# TDA2004.net
KiCad netlist of a schematic drawn in Altium Designer
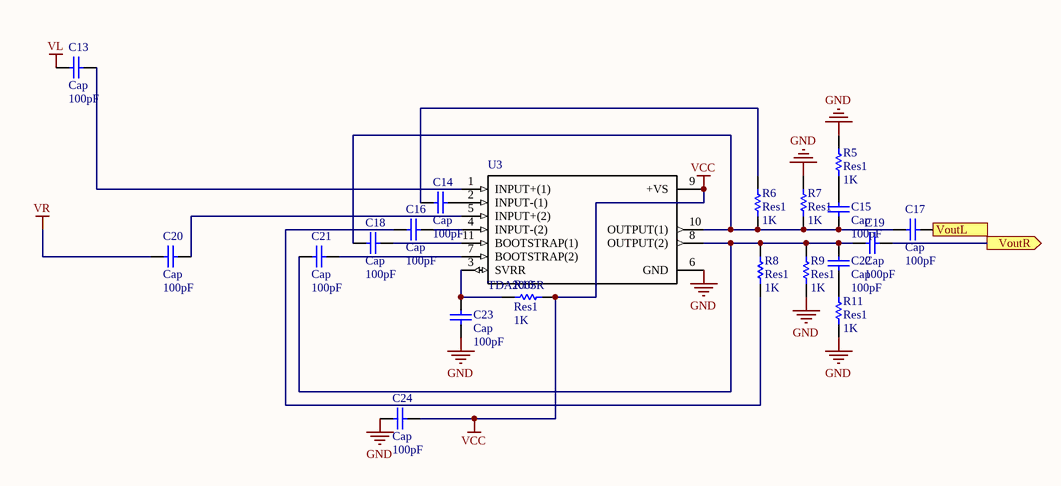
[diagram p0: TDA2004.SchDoc]

(export (version "E")
  (design (tool "Eeschema 10.0.6"))
  (components
    (comp (ref "C13")
      (value "Cap")
      (footprint "RAD-0.3")
      (description "Capacitor")
      (fields (field (name "ALTIUM_VALUE") "100pF") (field (name "PUBLISHER") "Altium Limited"))
      (libsource (lib "Miscellaneous Devices") (part "Cap"))
    )
    (comp (ref "C14")
      (value "Cap")
      (footprint "RAD-0.3")
      (description "Capacitor")
      (fields (field (name "ALTIUM_VALUE") "100pF") (field (name "PUBLISHER") "Altium Limited"))
      (libsource (lib "Miscellaneous Devices") (part "Cap"))
    )
    (comp (ref "C15")
      (value "Cap")
      (footprint "RAD-0.3")
      (description "Capacitor")
      (fields (field (name "ALTIUM_VALUE") "100pF") (field (name "PUBLISHER") "Altium Limited"))
      (libsource (lib "Miscellaneous Devices") (part "Cap"))
    )
    (comp (ref "C16")
      (value "Cap")
      (footprint "RAD-0.3")
      (description "Capacitor")
      (fields (field (name "ALTIUM_VALUE") "100pF") (field (name "PUBLISHER") "Altium Limited"))
      (libsource (lib "Miscellaneous Devices") (part "Cap"))
    )
    (comp (ref "C17")
      (value "Cap")
      (footprint "RAD-0.3")
      (description "Capacitor")
      (fields (field (name "ALTIUM_VALUE") "100pF") (field (name "PUBLISHER") "Altium Limited"))
      (libsource (lib "Miscellaneous Devices") (part "Cap"))
    )
    (comp (ref "C18")
      (value "Cap")
      (footprint "RAD-0.3")
      (description "Capacitor")
      (fields (field (name "ALTIUM_VALUE") "100pF") (field (name "PUBLISHER") "Altium Limited"))
      (libsource (lib "Miscellaneous Devices") (part "Cap"))
    )
    (comp (ref "C19")
      (value "Cap")
      (footprint "RAD-0.3")
      (description "Capacitor")
      (fields (field (name "ALTIUM_VALUE") "100pF") (field (name "PUBLISHER") "Altium Limited"))
      (libsource (lib "Miscellaneous Devices") (part "Cap"))
    )
    (comp (ref "C20")
      (value "Cap")
      (footprint "RAD-0.3")
      (description "Capacitor")
      (fields (field (name "ALTIUM_VALUE") "100pF") (field (name "PUBLISHER") "Altium Limited"))
      (libsource (lib "Miscellaneous Devices") (part "Cap"))
    )
    (comp (ref "C21")
      (value "Cap")
      (footprint "RAD-0.3")
      (description "Capacitor")
      (fields (field (name "ALTIUM_VALUE") "100pF") (field (name "PUBLISHER") "Altium Limited"))
      (libsource (lib "Miscellaneous Devices") (part "Cap"))
    )
    (comp (ref "C22")
      (value "Cap")
      (footprint "RAD-0.3")
      (description "Capacitor")
      (fields (field (name "ALTIUM_VALUE") "100pF") (field (name "PUBLISHER") "Altium Limited"))
      (libsource (lib "Miscellaneous Devices") (part "Cap"))
    )
    (comp (ref "C23")
      (value "Cap")
      (footprint "RAD-0.3")
      (description "Capacitor")
      (fields (field (name "ALTIUM_VALUE") "100pF") (field (name "PUBLISHER") "Altium Limited"))
      (libsource (lib "Miscellaneous Devices") (part "Cap"))
    )
    (comp (ref "C24")
      (value "Cap")
      (footprint "RAD-0.3")
      (description "Capacitor")
      (fields (field (name "ALTIUM_VALUE") "100pF") (field (name "PUBLISHER") "Altium Limited"))
      (libsource (lib "Miscellaneous Devices") (part "Cap"))
    )
    (comp (ref "R5")
      (value "Res1")
      (footprint "AXIAL-0.3")
      (description "Resistor")
      (fields (field (name "ALTIUM_VALUE") "1K") (field (name "PUBLISHER") "Altium Limited"))
      (libsource (lib "Miscellaneous Devices") (part "Res1"))
    )
    (comp (ref "R6")
      (value "Res1")
      (footprint "AXIAL-0.3")
      (description "Resistor")
      (fields (field (name "ALTIUM_VALUE") "1K") (field (name "PUBLISHER") "Altium Limited"))
      (libsource (lib "Miscellaneous Devices") (part "Res1"))
    )
    (comp (ref "R7")
      (value "Res1")
      (footprint "AXIAL-0.3")
      (description "Resistor")
      (fields (field (name "ALTIUM_VALUE") "1K") (field (name "PUBLISHER") "Altium Limited"))
      (libsource (lib "Miscellaneous Devices") (part "Res1"))
    )
    (comp (ref "R8")
      (value "Res1")
      (footprint "AXIAL-0.3")
      (description "Resistor")
      (fields (field (name "ALTIUM_VALUE") "1K") (field (name "PUBLISHER") "Altium Limited"))
      (libsource (lib "Miscellaneous Devices") (part "Res1"))
    )
    (comp (ref "R9")
      (value "Res1")
      (footprint "AXIAL-0.3")
      (description "Resistor")
      (fields (field (name "ALTIUM_VALUE") "1K") (field (name "PUBLISHER") "Altium Limited"))
      (libsource (lib "Miscellaneous Devices") (part "Res1"))
    )
    (comp (ref "R10")
      (value "Res1")
      (footprint "AXIAL-0.3")
      (description "Resistor")
      (fields (field (name "ALTIUM_VALUE") "1K") (field (name "PUBLISHER") "Altium Limited"))
      (libsource (lib "Miscellaneous Devices") (part "Res1"))
    )
    (comp (ref "R11")
      (value "Res1")
      (footprint "AXIAL-0.3")
      (description "Resistor")
      (fields (field (name "ALTIUM_VALUE") "1K") (field (name "PUBLISHER") "Altium Limited"))
      (libsource (lib "Miscellaneous Devices") (part "Res1"))
    )
    (comp (ref "U3")
      (value "TDA2005R")
      (footprint "TO170P500X1990X2138-11P")
      (description "Audio Amp Speaker 1-CH Mono/2-CH Stereo 22W Class-B Automotive 11-Pin_11+Tab_ MULTIWATT Tube")
      (fields (field (name "MF") "STMicroelectronics"))
      (libsource (lib "TDA2005R") (part "TDA2005R"))
    )
  )
  (nets
    (net (code "1") (name "/VoutL") (class "Default")
      (node (ref "C17") (pin "2") (pinfunction "2_2") (pintype "passive"))
    )
    (net (code "2") (name "/VoutR") (class "Default")
      (node (ref "C19") (pin "2") (pinfunction "2_2") (pintype "passive"))
    )
    (net (code "3") (name "GND") (class "Default")
      (node (ref "C23") (pin "1") (pinfunction "1_1") (pintype "passive"))
      (node (ref "C24") (pin "1") (pinfunction "1_1") (pintype "passive"))
      (node (ref "R11") (pin "1") (pinfunction "1_1") (pintype "passive"))
      (node (ref "R5") (pin "2") (pinfunction "2_2") (pintype "passive"))
      (node (ref "R7") (pin "2") (pinfunction "2_2") (pintype "passive"))
      (node (ref "R9") (pin "1") (pinfunction "1_1") (pintype "passive"))
      (node (ref "U3") (pin "6") (pinfunction "GND_6") (pintype "power_in"))
    )
    (net (code "4") (name "Net-(C14-Pad1)") (class "Default")
      (node (ref "C14") (pin "1") (pinfunction "1_1") (pintype "passive"))
      (node (ref "R6") (pin "2") (pinfunction "2_2") (pintype "passive"))
    )
    (net (code "5") (name "Net-(C15-Pad2)") (class "Default")
      (node (ref "C15") (pin "2") (pinfunction "2_2") (pintype "passive"))
      (node (ref "R5") (pin "1") (pinfunction "1_1") (pintype "passive"))
    )
    (net (code "6") (name "Net-(C16-Pad1)") (class "Default")
      (node (ref "C16") (pin "1") (pinfunction "1_1") (pintype "passive"))
      (node (ref "R8") (pin "1") (pinfunction "1_1") (pintype "passive"))
    )
    (net (code "7") (name "Net-(C22-Pad1)") (class "Default")
      (node (ref "C22") (pin "1") (pinfunction "1_1") (pintype "passive"))
      (node (ref "R11") (pin "2") (pinfunction "2_2") (pintype "passive"))
    )
    (net (code "8") (name "Net-(U3-BOOTSTRAP(1))") (class "Default")
      (node (ref "C18") (pin "2") (pinfunction "2_2") (pintype "passive"))
      (node (ref "U3") (pin "11") (pinfunction "BOOTSTRAP(1)_11") (pintype "input"))
    )
    (net (code "9") (name "Net-(U3-BOOTSTRAP(2))") (class "Default")
      (node (ref "C21") (pin "2") (pinfunction "2_2") (pintype "passive"))
      (node (ref "U3") (pin "7") (pinfunction "BOOTSTRAP(2)_7") (pintype "input"))
    )
    (net (code "10") (name "Net-(U3-INPUT+(1))") (class "Default")
      (node (ref "C13") (pin "2") (pinfunction "2_2") (pintype "passive"))
      (node (ref "U3") (pin "1") (pinfunction "INPUT+(1)_1") (pintype "input"))
    )
    (net (code "11") (name "Net-(U3-INPUT+(2))") (class "Default")
      (node (ref "C20") (pin "2") (pinfunction "2_2") (pintype "passive"))
      (node (ref "U3") (pin "5") (pinfunction "INPUT+(2)_5") (pintype "input"))
    )
    (net (code "12") (name "Net-(U3-INPUT-(1))") (class "Default")
      (node (ref "C14") (pin "2") (pinfunction "2_2") (pintype "passive"))
      (node (ref "U3") (pin "2") (pinfunction "INPUT-(1)_2") (pintype "input"))
    )
    (net (code "13") (name "Net-(U3-INPUT-(2))") (class "Default")
      (node (ref "C16") (pin "2") (pinfunction "2_2") (pintype "passive"))
      (node (ref "U3") (pin "4") (pinfunction "INPUT-(2)_4") (pintype "input"))
    )
    (net (code "14") (name "Net-(U3-OUTPUT(1))") (class "Default")
      (node (ref "C15") (pin "1") (pinfunction "1_1") (pintype "passive"))
      (node (ref "C17") (pin "1") (pinfunction "1_1") (pintype "passive"))
      (node (ref "C18") (pin "1") (pinfunction "1_1") (pintype "passive"))
      (node (ref "R6") (pin "1") (pinfunction "1_1") (pintype "passive"))
      (node (ref "R7") (pin "1") (pinfunction "1_1") (pintype "passive"))
      (node (ref "U3") (pin "10") (pinfunction "OUTPUT(1)_10") (pintype "output"))
    )
    (net (code "15") (name "Net-(U3-OUTPUT(2))") (class "Default")
      (node (ref "C19") (pin "1") (pinfunction "1_1") (pintype "passive"))
      (node (ref "C21") (pin "1") (pinfunction "1_1") (pintype "passive"))
      (node (ref "C22") (pin "2") (pinfunction "2_2") (pintype "passive"))
      (node (ref "R8") (pin "2") (pinfunction "2_2") (pintype "passive"))
      (node (ref "R9") (pin "2") (pinfunction "2_2") (pintype "passive"))
      (node (ref "U3") (pin "8") (pinfunction "OUTPUT(2)_8") (pintype "output"))
    )
    (net (code "16") (name "Net-(U3-SVRR)") (class "Default")
      (node (ref "C23") (pin "2") (pinfunction "2_2") (pintype "passive"))
      (node (ref "R10") (pin "1") (pinfunction "1_1") (pintype "passive"))
      (node (ref "U3") (pin "3") (pinfunction "SVRR_3") (pintype "bidirectional"))
    )
    (net (code "17") (name "VCC") (class "Default")
      (node (ref "C24") (pin "2") (pinfunction "2_2") (pintype "passive"))
      (node (ref "R10") (pin "2") (pinfunction "2_2") (pintype "passive"))
      (node (ref "U3") (pin "9") (pinfunction "+VS_9") (pintype "power_in"))
    )
    (net (code "18") (name "VL") (class "Default")
      (node (ref "C13") (pin "1") (pinfunction "1_1") (pintype "passive"))
    )
    (net (code "19") (name "VR") (class "Default")
      (node (ref "C20") (pin "1") (pinfunction "1_1") (pintype "passive"))
    )
  )
)
